# ESP_unit.net
KiCad netlist of a schematic drawn in Altium Designer
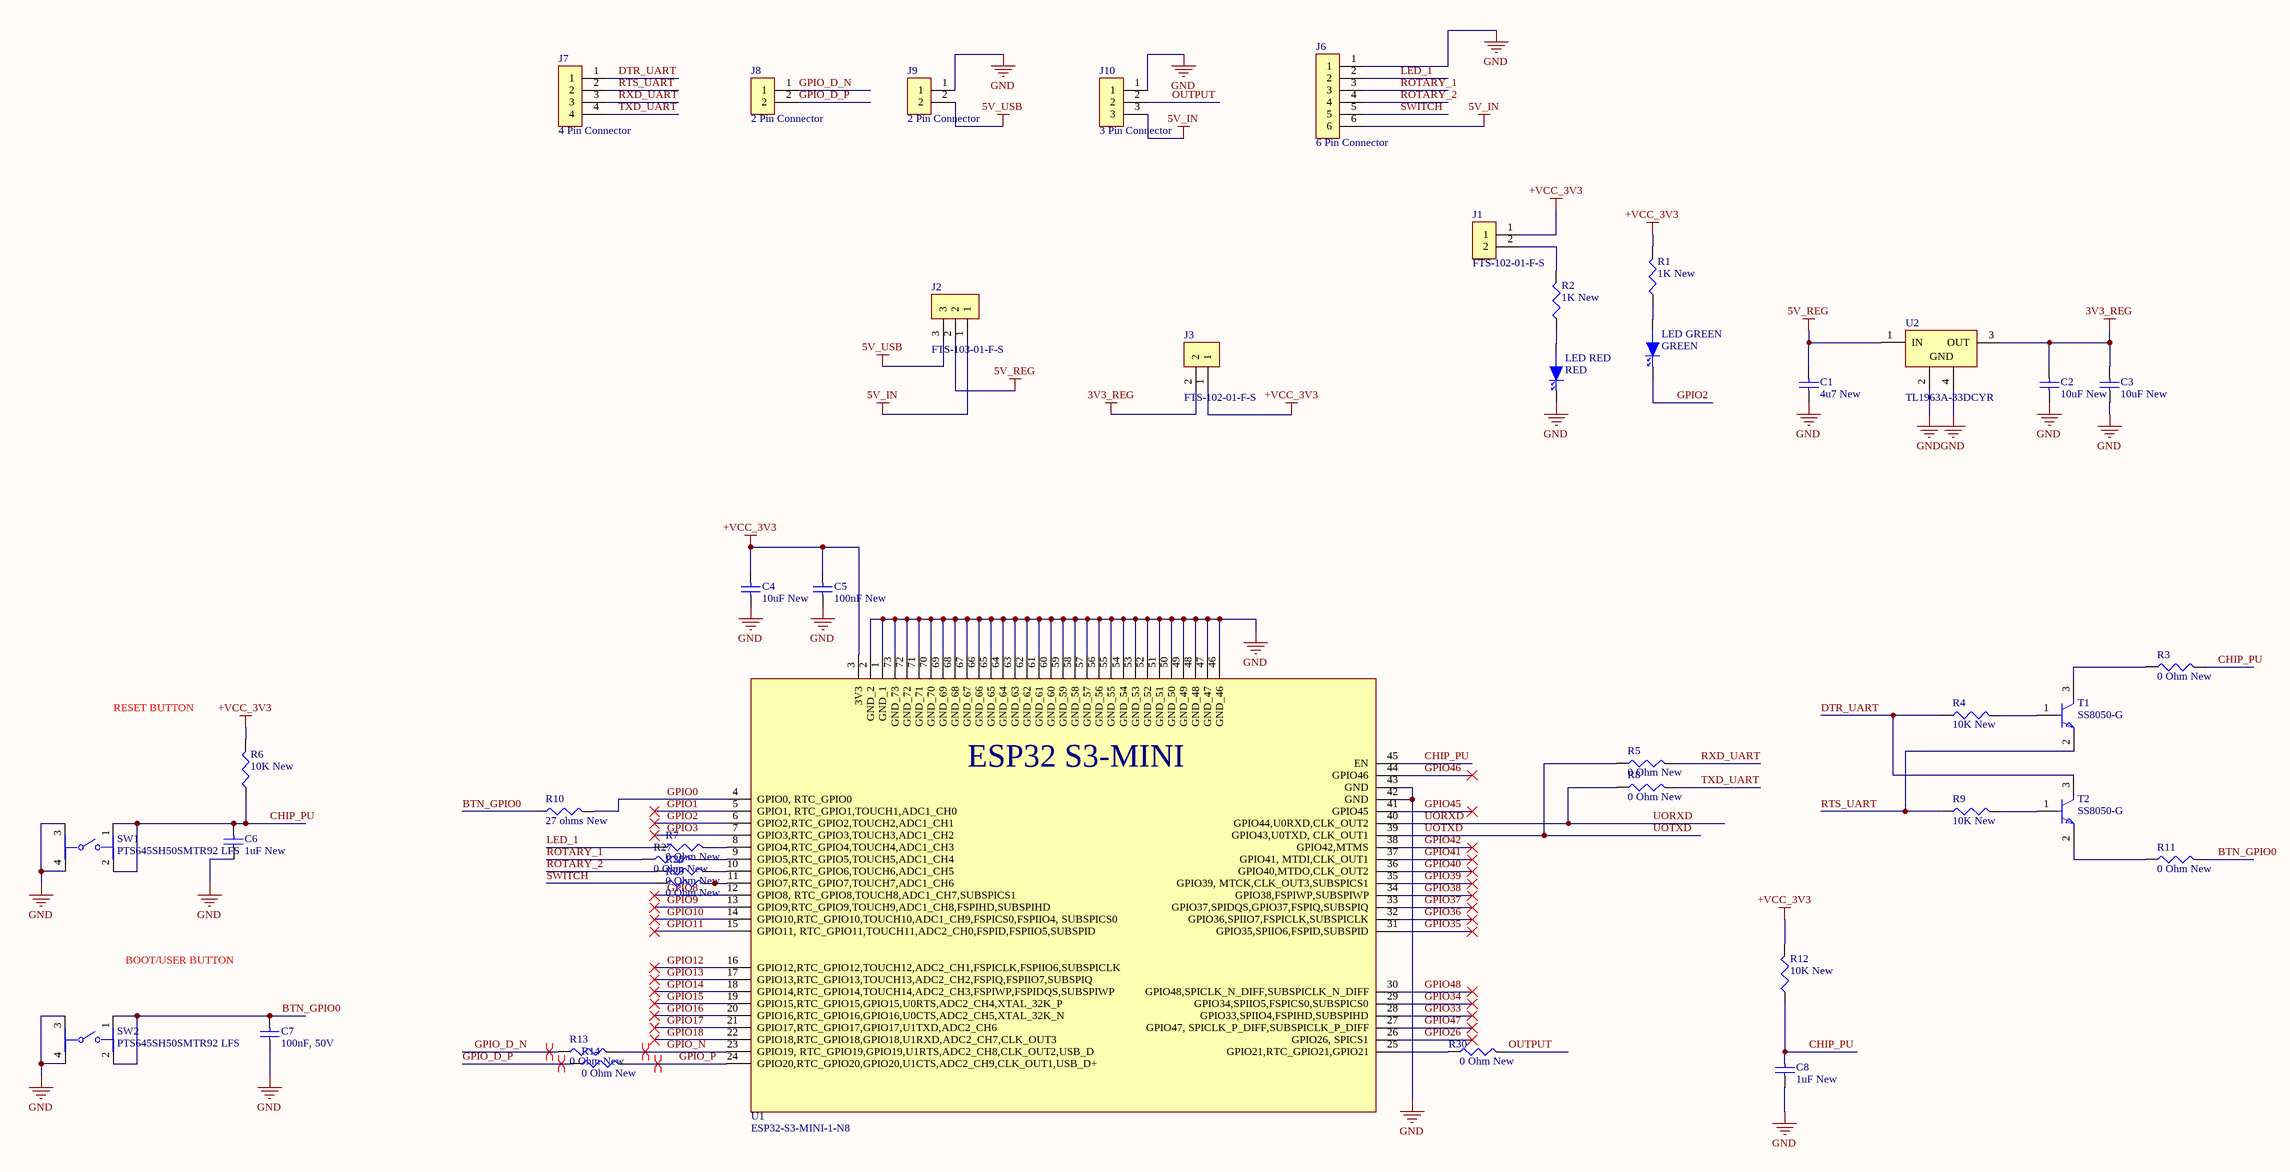
[diagram p0: ESP unit.SchDoc]

(export (version "E")
  (design (tool "Eeschema 10.0.6"))
  (components
    (comp (ref "C1")
      (value "4u7 New")
      (footprint "FP-CC0805-0_85-IPC_A")
      (fields
        (field (name "MANUFACTURER") "Yageo")
        (field (name "MANUFACTURER PART NUMBER") "CC0805KKX5R8BB475")
        (field (name "LCSC PART NUMBER") "C132173")
      )
      (libsource (lib "Schlib1") (part "CC0805KKX5R8BB475"))
    )
    (comp (ref "C2")
      (value "10uF New")
      (footprint "FP-CC0805-0_85-IPC_A")
      (fields
        (field (name "MANUFACTURER") "Yageo")
        (field (name "MANUFACTURER PART NUMBER") "CC0805ZKY5V6BB106")
        (field (name "LCSC PART NUMBER") "C88484")
      )
      (libsource (lib "Schlib1") (part "CC0805ZKY5V6BB106"))
    )
    (comp (ref "C3")
      (value "10uF New")
      (footprint "FP-CC0805-0_85-IPC_A")
      (fields
        (field (name "MANUFACTURER") "Yageo")
        (field (name "MANUFACTURER PART NUMBER") "CC0805ZKY5V6BB106")
        (field (name "LCSC PART NUMBER") "C88484")
      )
      (libsource (lib "Schlib1") (part "CC0805ZKY5V6BB106"))
    )
    (comp (ref "C4")
      (value "10uF New")
      (footprint "FP-CC0805-0_85-IPC_A")
      (fields
        (field (name "MANUFACTURER") "Yageo")
        (field (name "MANUFACTURER PART NUMBER") "CC0805ZKY5V6BB106")
        (field (name "LCSC PART NUMBER") "C88484")
      )
      (libsource (lib "Schlib1") (part "CC0805ZKY5V6BB106"))
    )
    (comp (ref "C5")
      (value "100nF New")
      (footprint "FP-CC0805-0_85-IPC_A")
      (fields
        (field (name "MANUFACTURER") "Yageo")
        (field (name "MANUFACTURER PART NUMBER") "CC0805KRX7R9BB104")
        (field (name "LCSC PART NUMBER") "C49678")
      )
      (libsource (lib "Schlib1") (part "CC0805KRX7R9BB104"))
    )
    (comp (ref "C6")
      (value "1uF New")
      (footprint "FP-CC0805-0_85-IPC_A")
      (fields
        (field (name "MANUFACTURER") "Yageo")
        (field (name "MANUFACTURER PART NUMBER") "CC0805KKX7R7BB105")
        (field (name "LCSC PART NUMBER") "C94122")
      )
      (libsource (lib "Schlib1") (part "CC0805KKX7R7BB105"))
    )
    (comp (ref "C7")
      (value "100nF, 50V")
      (footprint "CAPC1005X55N")
      (description "CAP CER 0.1UF 50V X7R 0402")
      (fields
        (field (name "MANUFACTURER") "Samsung")
        (field (name "MANUFACTURER PART NUMBER") "CL05B104KB54PNC")
      )
      (libsource (lib "Schlib1") (part "CL05B104KB54PNC"))
    )
    (comp (ref "C8")
      (value "1uF New")
      (footprint "FP-CC0805-0_85-IPC_A")
      (fields
        (field (name "MANUFACTURER") "Yageo")
        (field (name "MANUFACTURER PART NUMBER") "CC0805KKX7R7BB105")
        (field (name "LCSC PART NUMBER") "C94122")
      )
      (libsource (lib "Schlib1") (part "CC0805KKX7R7BB105"))
    )
    (comp (ref "J1")
      (value "FTS-102-01-F-S")
      (footprint "2 Pin Connector Jumper")
      (description "CONN HEADER VERT 2POS 1.27MM")
      (fields (field (name "MANUFACTURER") "Samtec") (field (name "LCSC PART NUMBER") "C6045317"))
      (libsource (lib "Schlib1") (part "FTS-102-01-F-S"))
    )
    (comp (ref "J2")
      (value "FTS-103-01-F-S")
      (footprint "3 Pin Connector Jumper - duplicate")
      (description "CONN HEADER VERT 3POS 1.27MM")
      (fields (field (name "MANUFACTURER") "Samtec") (field (name "LCSC PART NUMBER") "C3333578"))
      (libsource (lib "Schlib1") (part "FTS-103-01-F-S"))
    )
    (comp (ref "J3")
      (value "FTS-102-01-F-S")
      (footprint "2 Pin Connector Jumper")
      (description "CONN HEADER VERT 2POS 1.27MM")
      (fields (field (name "MANUFACTURER") "Samtec") (field (name "LCSC PART NUMBER") "C6045317"))
      (libsource (lib "") (part "FTS-102-01-F-S_1"))
    )
    (comp (ref "J6")
      (value "6 Pin Connector")
      (footprint "SAMTEC_HTSW-106-07-G-S")
      (fields
        (field (name "MANUFACTURER") "Samtec")
        (field (name "MANUFACTURER PART NUMBER") "HTSW-106-07-G-S")
        (field (name "LCSC PART NUMBER") "C3334125")
      )
      (libsource (lib "Schlib1") (part "HTSW-106-07-G-S"))
    )
    (comp (ref "J7")
      (value "4 Pin Connector")
      (footprint "SAMTEC_HTSW-104-07-G-S")
      (fields
        (field (name "MANUFACTURER") "Samtec")
        (field (name "MANUFACTURER PART NUMBER") "HTSW-104-07-G-S")
        (field (name "LCSC PART NUMBER") "C3335226")
      )
      (libsource (lib "Schlib1") (part "HTSW-104-07-G-S"))
    )
    (comp (ref "J8")
      (value "2 Pin Connector")
      (footprint "SAMTEC_HTSW-102-07-G-S")
      (description "Board Connector, 2 Contact(s), 1 Row(s), Male, Straight, 0.1 inch Pitch, Solder Terminal")
      (fields
        (field (name "MANUFACTURER") "Samtec")
        (field (name "MANUFACTURER PART NUMBER") "HTSW-102-07-G-S")
      )
      (libsource (lib "Schlib1") (part "HTSW-102-07-G-S"))
    )
    (comp (ref "J9")
      (value "2 Pin Connector")
      (footprint "SAMTEC_HTSW-102-07-G-S")
      (description "Board Connector, 2 Contact(s), 1 Row(s), Male, Straight, 0.1 inch Pitch, Solder Terminal")
      (fields
        (field (name "MANUFACTURER") "Samtec")
        (field (name "MANUFACTURER PART NUMBER") "HTSW-102-07-G-S")
      )
      (libsource (lib "Schlib1") (part "HTSW-102-07-G-S"))
    )
    (comp (ref "J10")
      (value "3 Pin Connector")
      (footprint "SAMTEC_HTSW-103-XX-X-S")
      (fields
        (field (name "MANUFACTURER") "Samtec")
        (field (name "MANUFACTURER PART NUMBER") "HTSW-103-07-G-S")
        (field (name "LCSC PART NUMBER") "C5714562")
      )
      (libsource (lib "Schlib1") (part "HTSW-103-07-G-S"))
    )
    (comp (ref "LED GREEN")
      (value "GREEN")
      (footprint "LED 0402G")
      (description "LED YLW-GRN 0402 SMD")
      (fields
        (field (name "MANUFACTURER") "Vishay")
        (field (name "MANUFACTURER PART NUMBER") "VLMG1500-GS08")
      )
      (libsource (lib "Schlib1") (part "VLMG1500-GS08"))
    )
    (comp (ref "LED RED")
      (value "RED")
      (footprint "LED 0402R")
      (description "LED RED 0402 SMD")
      (fields
        (field (name "MANUFACTURER") "Vishay")
        (field (name "MANUFACTURER PART NUMBER") "VLMS1500-GS08")
      )
      (libsource (lib "Schlib1") (part "VLMS1500-GS08"))
    )
    (comp (ref "R1")
      (value "1K New")
      (footprint "RESC2012X60N")
      (fields
        (field (name "MANUFACTURER") "Yageo")
        (field (name "MANUFACTURER PART NUMBER") "RC0805FR-071KL")
        (field (name "TOLERANCE") "1%")
      )
      (libsource (lib "Schlib1") (part "RC0805FR-071KL"))
    )
    (comp (ref "R2")
      (value "1K New")
      (footprint "RESC2012X60N")
      (fields
        (field (name "MANUFACTURER") "Yageo")
        (field (name "MANUFACTURER PART NUMBER") "RC0805FR-071KL")
        (field (name "TOLERANCE") "1%")
      )
      (libsource (lib "Schlib1") (part "RC0805FR-071KL"))
    )
    (comp (ref "R3")
      (value "0 Ohm New")
      (footprint "RESC2012X60N")
      (description "125mW Thick Film Resistors 150V ±5% 0Ω 0805 Chip Resistor - Surface Mount ROHS")
      (fields
        (field (name "MANUFACTURER") "Yageo")
        (field (name "MANUFACTURER PART NUMBER") "RC0805JR-070RL")
      )
      (libsource (lib "Schlib1") (part "RC0805JR-070RL"))
    )
    (comp (ref "R4")
      (value "10K New")
      (footprint "RESC2012X60N")
      (fields
        (field (name "MANUFACTURER") "Yageo")
        (field (name "MANUFACTURER PART NUMBER") "RE0805FRE0710KL")
        (field (name "TOLERANCE") "1%")
      )
      (libsource (lib "Schlib1") (part "RE0805FRE0710KL"))
    )
    (comp (ref "R5")
      (value "0 Ohm New")
      (footprint "RESC2012X60N")
      (description "125mW Thick Film Resistors 150V ±5% 0Ω 0805 Chip Resistor - Surface Mount ROHS")
      (fields
        (field (name "MANUFACTURER") "Yageo")
        (field (name "MANUFACTURER PART NUMBER") "RC0805JR-070RL")
      )
      (libsource (lib "Schlib1") (part "RC0805JR-070RL"))
    )
    (comp (ref "R6")
      (value "10K New")
      (footprint "RESC2012X60N")
      (fields
        (field (name "MANUFACTURER") "Yageo")
        (field (name "MANUFACTURER PART NUMBER") "RE0805FRE0710KL")
        (field (name "TOLERANCE") "1%")
      )
      (libsource (lib "Schlib1") (part "RE0805FRE0710KL"))
    )
    (comp (ref "R7")
      (value "0 Ohm New")
      (footprint "RESC2012X60N")
      (description "125mW Thick Film Resistors 150V ±5% 0Ω 0805 Chip Resistor - Surface Mount ROHS")
      (fields
        (field (name "MANUFACTURER") "Yageo")
        (field (name "MANUFACTURER PART NUMBER") "RC0805JR-070RL")
      )
      (libsource (lib "Schlib1") (part "RC0805JR-070RL"))
    )
    (comp (ref "R8")
      (value "0 Ohm New")
      (footprint "RESC2012X60N")
      (description "125mW Thick Film Resistors 150V ±5% 0Ω 0805 Chip Resistor - Surface Mount ROHS")
      (fields
        (field (name "MANUFACTURER") "Yageo")
        (field (name "MANUFACTURER PART NUMBER") "RC0805JR-070RL")
      )
      (libsource (lib "Schlib1") (part "RC0805JR-070RL"))
    )
    (comp (ref "R9")
      (value "10K New")
      (footprint "RESC2012X60N")
      (fields
        (field (name "MANUFACTURER") "Yageo")
        (field (name "MANUFACTURER PART NUMBER") "RE0805FRE0710KL")
        (field (name "TOLERANCE") "1%")
      )
      (libsource (lib "Schlib1") (part "RE0805FRE0710KL"))
    )
    (comp (ref "R10")
      (value "27 ohms New")
      (footprint "RESC2012X60N")
      (fields
        (field (name "MANUFACTURER") "Yageo")
        (field (name "MANUFACTURER PART NUMBER") "RC0805FR-0727RL")
        (field (name "TOLERANCE") "1%")
      )
      (libsource (lib "Schlib1") (part "RC0805FR-0727RL"))
    )
    (comp (ref "R11")
      (value "0 Ohm New")
      (footprint "RESC2012X60N")
      (description "125mW Thick Film Resistors 150V ±5% 0Ω 0805 Chip Resistor - Surface Mount ROHS")
      (fields
        (field (name "MANUFACTURER") "Yageo")
        (field (name "MANUFACTURER PART NUMBER") "RC0805JR-070RL")
      )
      (libsource (lib "Schlib1") (part "RC0805JR-070RL"))
    )
    (comp (ref "R12")
      (value "10K New")
      (footprint "RESC2012X60N")
      (fields
        (field (name "MANUFACTURER") "Yageo")
        (field (name "MANUFACTURER PART NUMBER") "RE0805FRE0710KL")
        (field (name "TOLERANCE") "1%")
      )
      (libsource (lib "Schlib1") (part "RE0805FRE0710KL"))
    )
    (comp (ref "R13")
      (value "0 Ohm New")
      (footprint "RESC2012X60N")
      (description "125mW Thick Film Resistors 150V ±5% 0Ω 0805 Chip Resistor - Surface Mount ROHS")
      (fields
        (field (name "MANUFACTURER") "Yageo")
        (field (name "MANUFACTURER PART NUMBER") "RC0805JR-070RL")
      )
      (libsource (lib "Schlib1") (part "RC0805JR-070RL"))
    )
    (comp (ref "R14")
      (value "0 Ohm New")
      (footprint "RESC2012X60N")
      (description "125mW Thick Film Resistors 150V ±5% 0Ω 0805 Chip Resistor - Surface Mount ROHS")
      (fields
        (field (name "MANUFACTURER") "Yageo")
        (field (name "MANUFACTURER PART NUMBER") "RC0805JR-070RL")
      )
      (libsource (lib "Schlib1") (part "RC0805JR-070RL"))
    )
    (comp (ref "R27")
      (value "0 Ohm New")
      (footprint "RESC2012X60N")
      (description "125mW Thick Film Resistors 150V ±5% 0Ω 0805 Chip Resistor - Surface Mount ROHS")
      (fields
        (field (name "MANUFACTURER") "Yageo")
        (field (name "MANUFACTURER PART NUMBER") "RC0805JR-070RL")
      )
      (libsource (lib "Schlib1") (part "RC0805JR-070RL"))
    )
    (comp (ref "R28")
      (value "0 Ohm New")
      (footprint "RESC2012X60N")
      (description "125mW Thick Film Resistors 150V ±5% 0Ω 0805 Chip Resistor - Surface Mount ROHS")
      (fields
        (field (name "MANUFACTURER") "Yageo")
        (field (name "MANUFACTURER PART NUMBER") "RC0805JR-070RL")
      )
      (libsource (lib "Schlib1") (part "RC0805JR-070RL"))
    )
    (comp (ref "R29")
      (value "0 Ohm New")
      (footprint "RESC2012X60N")
      (description "125mW Thick Film Resistors 150V ±5% 0Ω 0805 Chip Resistor - Surface Mount ROHS")
      (fields
        (field (name "MANUFACTURER") "Yageo")
        (field (name "MANUFACTURER PART NUMBER") "RC0805JR-070RL")
      )
      (libsource (lib "Schlib1") (part "RC0805JR-070RL"))
    )
    (comp (ref "R30")
      (value "0 Ohm New")
      (footprint "RESC2012X60N")
      (description "125mW Thick Film Resistors 150V ±5% 0Ω 0805 Chip Resistor - Surface Mount ROHS")
      (fields
        (field (name "MANUFACTURER") "Yageo")
        (field (name "MANUFACTURER PART NUMBER") "RC0805JR-070RL")
      )
      (libsource (lib "Schlib1") (part "RC0805JR-070RL"))
    )
    (comp (ref "SW1")
      (value "PTS645SH50SMTR92 LFS")
      (footprint "FP-PTS645SH50SMTR92LFS-MFG")
      (description "SWITCH TACTILE SPST-NO 0.05A 12V")
      (fields
        (field (name "MANUFACTURER") "ITT C&K")
        (field (name "MANUFACTURER PART NUMBER") "PTS645SH50SMTR92LFS")
      )
      (libsource (lib "Schlib1") (part "PTS645SH50SMTR92LFS"))
    )
    (comp (ref "SW2")
      (value "PTS645SH50SMTR92 LFS")
      (footprint "FP-PTS645SH50SMTR92LFS-MFG")
      (description "SWITCH TACTILE SPST-NO 0.05A 12V")
      (fields
        (field (name "MANUFACTURER") "ITT C&K")
        (field (name "MANUFACTURER PART NUMBER") "PTS645SH50SMTR92LFS")
      )
      (libsource (lib "Schlib1") (part "PTS645SH50SMTR92LFS"))
    )
    (comp (ref "T1")
      (value "SS8050-G")
      (footprint "FP-SS8050-G-IPC_B")
      (description "TRANS NPN 25V 1.5A SOT-23-3")
      (fields (field (name "MANUFACTURER") "Comchip") (field (name "LCSC PART NUMBER") "C164886"))
      (libsource (lib "Schlib1") (part "SS8050-G"))
    )
    (comp (ref "T2")
      (value "SS8050-G")
      (footprint "FP-SS8050-G-IPC_B")
      (description "TRANS NPN 25V 1.5A SOT-23-3")
      (fields (field (name "MANUFACTURER") "Comchip") (field (name "LCSC PART NUMBER") "C164886"))
      (libsource (lib "Schlib1") (part "SS8050-G"))
    )
    (comp (ref "U1")
      (value "ESP32-S3-MINI-1-N8")
      (footprint "XCVR_ESP32-S3-MINI-1-N8")
      (description "SMD module, ESP32-S3FN8, 8 MB SPI flash, PCB antenna")
      (fields (field (name "MANUFACTURER") "Espressif Systems") (field (name "LCSC PART NUMBER") "C2913206"))
      (libsource (lib "Schlib1") (part "ESP32-S3-MINI-1-N8"))
    )
    (comp (ref "U2")
      (value "TL1963A-33DCYR")
      (footprint "DCY0004A_N")
      (description "IC REG LIN 3.3V 1.5A SOT-223-4")
      (fields (field (name "MANUFACTURER") "Texas Instruments") (field (name "LCSC PART NUMBER") "C181262"))
      (libsource (lib "Schlib1") (part "TL1963A-33DCYR"))
    )
  )
  (nets
    (net (code "1") (name "+VCC_3V3") (class "Default")
      (node (ref "C4") (pin "2") (pinfunction "2_2") (pintype "passive"))
      (node (ref "C5") (pin "2") (pinfunction "2_2") (pintype "passive"))
      (node (ref "J1") (pin "1") (pinfunction "1_1") (pintype "passive"))
      (node (ref "J3") (pin "1") (pinfunction "1_1") (pintype "passive"))
      (node (ref "R1") (pin "2") (pinfunction "2_2") (pintype "passive"))
      (node (ref "R12") (pin "2") (pinfunction "2_2") (pintype "passive"))
      (node (ref "R6") (pin "2") (pinfunction "2_2") (pintype "passive"))
      (node (ref "U1") (pin "3") (pinfunction "3V3_3") (pintype "passive"))
    )
    (net (code "2") (name "/BTN_GPIO0") (class "Default")
      (node (ref "C7") (pin "2") (pinfunction "2_2") (pintype "passive"))
      (node (ref "R10") (pin "1") (pinfunction "1_1") (pintype "passive"))
      (node (ref "R11") (pin "2") (pinfunction "2_2") (pintype "passive"))
      (node (ref "SW2") (pin "1") (pinfunction "1_1") (pintype "passive"))
      (node (ref "SW2") (pin "2") (pinfunction "2_2") (pintype "passive"))
    )
    (net (code "3") (name "/CHIP_PU") (class "Default")
      (node (ref "C6") (pin "2") (pinfunction "2_2") (pintype "passive"))
      (node (ref "C8") (pin "2") (pinfunction "2_2") (pintype "passive"))
      (node (ref "R12") (pin "1") (pinfunction "1_1") (pintype "passive"))
      (node (ref "R3") (pin "2") (pinfunction "2_2") (pintype "passive"))
      (node (ref "R6") (pin "1") (pinfunction "1_1") (pintype "passive"))
      (node (ref "SW1") (pin "1") (pinfunction "1_1") (pintype "passive"))
      (node (ref "SW1") (pin "2") (pinfunction "2_2") (pintype "passive"))
      (node (ref "U1") (pin "45") (pinfunction "EN_45") (pintype "passive"))
    )
    (net (code "4") (name "/DTR_UART") (class "Default")
      (node (ref "J7") (pin "1") (pinfunction "1_1") (pintype "passive"))
      (node (ref "R4") (pin "1") (pinfunction "1_1") (pintype "passive"))
      (node (ref "T2") (pin "3") (pinfunction "C_3") (pintype "passive"))
    )
    (net (code "5") (name "/GPIO0") (class "Default")
      (node (ref "R10") (pin "2") (pinfunction "2_2") (pintype "passive"))
      (node (ref "U1") (pin "4") (pinfunction "GPIO0,_RTC_GPIO0_4") (pintype "passive"))
    )
    (net (code "6") (name "/GPIO1") (class "Default")
      (node (ref "U1") (pin "5") (pinfunction "GPIO1,_RTC_GPIO1,TOUCH1,ADC1_CH0_5") (pintype "passive+no_connect"))
    )
    (net (code "7") (name "/GPIO2") (class "Default")
      (node (ref "LED GREEN") (pin "1") (pinfunction "1_1") (pintype "passive"))
      (node (ref "U1") (pin "6") (pinfunction "GPIO2,RTC_GPIO2,TOUCH2,ADC1_CH1_6") (pintype "passive"))
    )
    (net (code "8") (name "/GPIO3") (class "Default")
      (node (ref "U1") (pin "7") (pinfunction "GPIO3,RTC_GPIO3,TOUCH3,ADC1_CH2_7") (pintype "passive+no_connect"))
    )
    (net (code "9") (name "/GPIO8") (class "Default")
      (node (ref "U1") (pin "12") (pinfunction "GPIO8,_RTC_GPIO8,TOUCH8,ADC1_CH7,SUBSPICS1_12") (pintype "passive+no_connect"))
    )
    (net (code "10") (name "/GPIO9") (class "Default")
      (node (ref "U1") (pin "13") (pinfunction "GPIO9,RTC_GPIO9,TOUCH9,ADC1_CH8,FSPIHD,SUBSPIHD_13") (pintype "passive+no_connect"))
    )
    (net (code "11") (name "/GPIO10") (class "Default")
      (node (ref "U1") (pin "14") (pinfunction "GPIO10,RTC_GPIO10,TOUCH10,ADC1_CH9,FSPICS0,FSPIIO4,_SUBSPICS0_14") (pintype "passive+no_connect"))
    )
    (net (code "12") (name "/GPIO11") (class "Default")
      (node (ref "U1") (pin "15") (pinfunction "GPIO11,_RTC_GPIO11,TOUCH11,ADC2_CH0,FSPID,FSPIIO5,SUBSPID_15") (pintype "passive+no_connect"))
    )
    (net (code "13") (name "/GPIO12") (class "Default")
      (node (ref "U1") (pin "16") (pinfunction "GPIO12,RTC_GPIO12,TOUCH12,ADC2_CH1,FSPICLK,FSPIIO6,SUBSPICLK_16") (pintype "passive+no_connect"))
    )
    (net (code "14") (name "/GPIO13") (class "Default")
      (node (ref "U1") (pin "17") (pinfunction "GPIO13,RTC_GPIO13,TOUCH13,ADC2_CH2,FSPIQ,FSPIIO7,SUBSPIQ_17") (pintype "passive+no_connect"))
    )
    (net (code "15") (name "/GPIO14") (class "Default")
      (node (ref "U1") (pin "18") (pinfunction "GPIO14,RTC_GPIO14,TOUCH14,ADC2_CH3,FSPIWP,FSPIDQS,SUBSPIWP_18") (pintype "passive+no_connect"))
    )
    (net (code "16") (name "/GPIO15") (class "Default")
      (node (ref "U1") (pin "19") (pinfunction "GPIO15,RTC_GPIO15,GPIO15,U0RTS,ADC2_CH4,XTAL_32K_P_19") (pintype "passive+no_connect"))
    )
    (net (code "17") (name "/GPIO16") (class "Default")
      (node (ref "U1") (pin "20") (pinfunction "GPIO16,RTC_GPIO16,GPIO16,U0CTS,ADC2_CH5,XTAL_32K_N_20") (pintype "passive+no_connect"))
    )
    (net (code "18") (name "/GPIO17") (class "Default")
      (node (ref "U1") (pin "21") (pinfunction "GPIO17,RTC_GPIO17,GPIO17,U1TXD,ADC2_CH6_21") (pintype "passive+no_connect"))
    )
    (net (code "19") (name "/GPIO18") (class "Default")
      (node (ref "U1") (pin "22") (pinfunction "GPIO18,RTC_GPIO18,GPIO18,U1RXD,ADC2_CH7,CLK_OUT3_22") (pintype "passive+no_connect"))
    )
    (net (code "20") (name "/GPIO26") (class "Default")
      (node (ref "U1") (pin "26") (pinfunction "GPIO26,_SPICS1_26") (pintype "passive+no_connect"))
    )
    (net (code "21") (name "/GPIO33") (class "Default")
      (node (ref "U1") (pin "28") (pinfunction "GPIO33,SPIIO4,FSPIHD,SUBSPIHD_28") (pintype "passive+no_connect"))
    )
    (net (code "22") (name "/GPIO34") (class "Default")
      (node (ref "U1") (pin "29") (pinfunction "GPIO34,SPIIO5,FSPICS0,SUBSPICS0_29") (pintype "passive+no_connect"))
    )
    (net (code "23") (name "/GPIO35") (class "Default")
      (node (ref "U1") (pin "31") (pinfunction "GPIO35,SPIIO6,FSPID,SUBSPID_31") (pintype "passive+no_connect"))
    )
    (net (code "24") (name "/GPIO36") (class "Default")
      (node (ref "U1") (pin "32") (pinfunction "GPIO36,SPIIO7,FSPICLK,SUBSPICLK_32") (pintype "passive+no_connect"))
    )
    (net (code "25") (name "/GPIO37") (class "Default")
      (node (ref "U1") (pin "33") (pinfunction "GPIO37,SPIDQS,GPIO37,FSPIQ,SUBSPIQ_33") (pintype "passive+no_connect"))
    )
    (net (code "26") (name "/GPIO38") (class "Default")
      (node (ref "U1") (pin "34") (pinfunction "GPIO38,FSPIWP,SUBSPIWP_34") (pintype "passive+no_connect"))
    )
    (net (code "27") (name "/GPIO39") (class "Default")
      (node (ref "U1") (pin "35") (pinfunction "GPIO39,_MTCK,CLK_OUT3,SUBSPICS1_35") (pintype "passive+no_connect"))
    )
    (net (code "28") (name "/GPIO40") (class "Default")
      (node (ref "U1") (pin "36") (pinfunction "GPIO40,MTDO,CLK_OUT2_36") (pintype "passive+no_connect"))
    )
    (net (code "29") (name "/GPIO41") (class "Default")
      (node (ref "U1") (pin "37") (pinfunction "GPIO41,_MTDI,CLK_OUT1_37") (pintype "passive+no_connect"))
    )
    (net (code "30") (name "/GPIO42") (class "Default")
      (node (ref "U1") (pin "38") (pinfunction "GPIO42,MTMS_38") (pintype "passive+no_connect"))
    )
    (net (code "31") (name "/GPIO45") (class "Default")
      (node (ref "U1") (pin "41") (pinfunction "GPIO45_41") (pintype "passive+no_connect"))
    )
    (net (code "32") (name "/GPIO46") (class "Default")
      (node (ref "U1") (pin "44") (pinfunction "GPIO46_44") (pintype "passive+no_connect"))
    )
    (net (code "33") (name "/GPIO47") (class "Default")
      (node (ref "U1") (pin "27") (pinfunction "GPIO47,_SPICLK_P_DIFF,SUBSPICLK_P_DIFF_27") (pintype "passive+no_connect"))
    )
    (net (code "34") (name "/GPIO48") (class "Default")
      (node (ref "U1") (pin "30") (pinfunction "GPIO48,SPICLK_N_DIFF,SUBSPICLK_N_DIFF_30") (pintype "passive+no_connect"))
    )
    (net (code "35") (name "/GPIO_D_N") (class "Default")
      (node (ref "J8") (pin "1") (pinfunction "1_1") (pintype "passive"))
      (node (ref "R13") (pin "1") (pinfunction "1_1") (pintype "passive"))
    )
    (net (code "36") (name "/GPIO_D_P") (class "Default")
      (node (ref "J8") (pin "2") (pinfunction "2_2") (pintype "passive"))
      (node (ref "R14") (pin "1") (pinfunction "1_1") (pintype "passive"))
    )
    (net (code "37") (name "/GPIO_N") (class "Default")
      (node (ref "R13") (pin "2") (pinfunction "2_2") (pintype "passive"))
      (node (ref "U1") (pin "23") (pinfunction "GPIO19,_RTC_GPIO19,GPIO19,U1RTS,ADC2_CH8,CLK_OUT2,USB_D_23") (pintype "passive"))
    )
    (net (code "38") (name "/GPIO_P") (class "Default")
      (node (ref "R14") (pin "2") (pinfunction "2_2") (pintype "passive"))
      (node (ref "U1") (pin "24") (pinfunction "GPIO20,RTC_GPIO20,GPIO20,U1CTS,ADC2_CH9,CLK_OUT1,USB_D+_24") (pintype "passive"))
    )
    (net (code "39") (name "/LED_1") (class "Default")
      (node (ref "J6") (pin "2") (pinfunction "2_2") (pintype "passive"))
      (node (ref "R7") (pin "1") (pinfunction "1_1") (pintype "passive"))
    )
    (net (code "40") (name "/OUTPUT") (class "Default")
      (node (ref "J10") (pin "2") (pinfunction "2_2") (pintype "passive"))
      (node (ref "R30") (pin "2") (pinfunction "2_2") (pintype "passive"))
    )
    (net (code "41") (name "/ROTARY_1") (class "Default")
      (node (ref "J6") (pin "3") (pinfunction "3_3") (pintype "passive"))
      (node (ref "R27") (pin "1") (pinfunction "1_1") (pintype "passive"))
    )
    (net (code "42") (name "/ROTARY_2") (class "Default")
      (node (ref "J6") (pin "4") (pinfunction "4_4") (pintype "passive"))
      (node (ref "R28") (pin "1") (pinfunction "1_1") (pintype "passive"))
    )
    (net (code "43") (name "/RTS_UART") (class "Default")
      (node (ref "J7") (pin "2") (pinfunction "2_2") (pintype "passive"))
      (node (ref "R9") (pin "1") (pinfunction "1_1") (pintype "passive"))
      (node (ref "T1") (pin "2") (pinfunction "E_2") (pintype "passive"))
    )
    (net (code "44") (name "/RXD_UART") (class "Default")
      (node (ref "J7") (pin "3") (pinfunction "3_3") (pintype "passive"))
      (node (ref "R5") (pin "2") (pinfunction "2_2") (pintype "passive"))
    )
    (net (code "45") (name "/SWITCH") (class "Default")
      (node (ref "J6") (pin "5") (pinfunction "5_5") (pintype "passive"))
      (node (ref "R29") (pin "1") (pinfunction "1_1") (pintype "passive"))
    )
    (net (code "46") (name "/TXD_UART") (class "Default")
      (node (ref "J7") (pin "4") (pinfunction "4_4") (pintype "passive"))
      (node (ref "R8") (pin "2") (pinfunction "2_2") (pintype "passive"))
    )
    (net (code "47") (name "/UORXD") (class "Default")
      (node (ref "R8") (pin "1") (pinfunction "1_1") (pintype "passive"))
      (node (ref "U1") (pin "40") (pinfunction "GPIO44,U0RXD,CLK_OUT2_40") (pintype "passive"))
    )
    (net (code "48") (name "/UOTXD") (class "Default")
      (node (ref "R5") (pin "1") (pinfunction "1_1") (pintype "passive"))
      (node (ref "U1") (pin "39") (pinfunction "GPIO43,U0TXD,_CLK_OUT1_39") (pintype "passive"))
    )
    (net (code "49") (name "3V3_REG") (class "Default")
      (node (ref "C2") (pin "2") (pinfunction "2_2") (pintype "passive"))
      (node (ref "C3") (pin "2") (pinfunction "2_2") (pintype "passive"))
      (node (ref "J3") (pin "2") (pinfunction "2_2") (pintype "passive"))
      (node (ref "U2") (pin "3") (pinfunction "OUT_3") (pintype "power_in"))
    )
    (net (code "50") (name "5V_IN") (class "Default")
      (node (ref "J10") (pin "3") (pinfunction "3_3") (pintype "passive"))
      (node (ref "J2") (pin "1") (pinfunction "1_1") (pintype "passive"))
      (node (ref "J6") (pin "6") (pinfunction "6_6") (pintype "passive"))
    )
    (net (code "51") (name "5V_REG") (class "Default")
      (node (ref "C1") (pin "2") (pinfunction "2_2") (pintype "passive"))
      (node (ref "J2") (pin "2") (pinfunction "2_2") (pintype "passive"))
      (node (ref "U2") (pin "1") (pinfunction "IN_1") (pintype "power_in"))
    )
    (net (code "52") (name "5V_USB") (class "Default")
      (node (ref "J2") (pin "3") (pinfunction "3_3") (pintype "passive"))
      (node (ref "J9") (pin "2") (pinfunction "2_2") (pintype "passive"))
    )
    (net (code "53") (name "GND") (class "Default")
      (node (ref "C1") (pin "1") (pinfunction "1_1") (pintype "passive"))
      (node (ref "C2") (pin "1") (pinfunction "1_1") (pintype "passive"))
      (node (ref "C3") (pin "1") (pinfunction "1_1") (pintype "passive"))
      (node (ref "C4") (pin "1") (pinfunction "1_1") (pintype "passive"))
      (node (ref "C5") (pin "1") (pinfunction "1_1") (pintype "passive"))
      (node (ref "C6") (pin "1") (pinfunction "1_1") (pintype "passive"))
      (node (ref "C7") (pin "1") (pinfunction "1_1") (pintype "passive"))
      (node (ref "C8") (pin "1") (pinfunction "1_1") (pintype "passive"))
      (node (ref "J10") (pin "1") (pinfunction "1_1") (pintype "passive"))
      (node (ref "J6") (pin "1") (pinfunction "1_1") (pintype "passive"))
      (node (ref "J9") (pin "1") (pinfunction "1_1") (pintype "passive"))
      (node (ref "LED RED") (pin "1") (pinfunction "1_1") (pintype "passive"))
      (node (ref "SW1") (pin "3") (pinfunction "3_3") (pintype "passive"))
      (node (ref "SW1") (pin "4") (pinfunction "4_4") (pintype "passive"))
      (node (ref "SW2") (pin "3") (pinfunction "3_3") (pintype "passive"))
      (node (ref "SW2") (pin "4") (pinfunction "4_4") (pintype "passive"))
      (node (ref "U1") (pin "1") (pinfunction "GND_1_1") (pintype "passive"))
      (node (ref "U1") (pin "2") (pinfunction "GND_2_2") (pintype "passive"))
      (node (ref "U1") (pin "42") (pinfunction "GND_42") (pintype "passive"))
      (node (ref "U1") (pin "43") (pinfunction "GND_43") (pintype "passive"))
      (node (ref "U1") (pin "46") (pinfunction "GND_46_46") (pintype "passive"))
      (node (ref "U1") (pin "47") (pinfunction "GND_47_47") (pintype "passive"))
      (node (ref "U1") (pin "48") (pinfunction "GND_48_48") (pintype "passive"))
      (node (ref "U1") (pin "49") (pinfunction "GND_49_49") (pintype "passive"))
      (node (ref "U1") (pin "50") (pinfunction "GND_50_50") (pintype "passive"))
      (node (ref "U1") (pin "51") (pinfunction "GND_51_51") (pintype "passive"))
      (node (ref "U1") (pin "52") (pinfunction "GND_52_52") (pintype "passive"))
      (node (ref "U1") (pin "53") (pinfunction "GND_53_53") (pintype "passive"))
      (node (ref "U1") (pin "54") (pinfunction "GND_54_54") (pintype "passive"))
      (node (ref "U1") (pin "55") (pinfunction "GND_55_55") (pintype "passive"))
      (node (ref "U1") (pin "56") (pinfunction "GND_56_56") (pintype "passive"))
      (node (ref "U1") (pin "57") (pinfunction "GND_57_57") (pintype "passive"))
      (node (ref "U1") (pin "58") (pinfunction "GND_58_58") (pintype "passive"))
      (node (ref "U1") (pin "59") (pinfunction "GND_59_59") (pintype "passive"))
      (node (ref "U1") (pin "60") (pinfunction "GND_60_60") (pintype "passive"))
      (node (ref "U1") (pin "61") (pinfunction "GND_61_61") (pintype "passive"))
      (node (ref "U1") (pin "62") (pinfunction "GND_62_62") (pintype "passive"))
      (node (ref "U1") (pin "63") (pinfunction "GND_63_63") (pintype "passive"))
      (node (ref "U1") (pin "64") (pinfunction "GND_64_64") (pintype "passive"))
      (node (ref "U1") (pin "65") (pinfunction "GND_65_65") (pintype "passive"))
      (node (ref "U1") (pin "66") (pinfunction "GND_66_66") (pintype "passive"))
      (node (ref "U1") (pin "67") (pinfunction "GND_67_67") (pintype "passive"))
      (node (ref "U1") (pin "68") (pinfunction "GND_68_68") (pintype "passive"))
      (node (ref "U1") (pin "69") (pinfunction "GND_69_69") (pintype "passive"))
      (node (ref "U1") (pin "70") (pinfunction "GND_70_70") (pintype "passive"))
      (node (ref "U1") (pin "71") (pinfunction "GND_71_71") (pintype "passive"))
      (node (ref "U1") (pin "72") (pinfunction "GND_72_72") (pintype "passive"))
      (node (ref "U1") (pin "73") (pinfunction "GND_73_73") (pintype "passive"))
      (node (ref "U2") (pin "2") (pinfunction "GND_2") (pintype "power_in"))
      (node (ref "U2") (pin "4") (pinfunction "GND_4") (pintype "power_in"))
    )
    (net (code "54") (name "Net-(J1-Pad2)") (class "Default")
      (node (ref "J1") (pin "2") (pinfunction "2_2") (pintype "passive"))
      (node (ref "R2") (pin "2") (pinfunction "2_2") (pintype "passive"))
    )
    (net (code "55") (name "Net-(LED GREEN-Pad2)") (class "Default")
      (node (ref "LED GREEN") (pin "2") (pinfunction "2_2") (pintype "passive"))
      (node (ref "R1") (pin "1") (pinfunction "1_1") (pintype "passive"))
    )
    (net (code "56") (name "Net-(LED RED-Pad2)") (class "Default")
      (node (ref "LED RED") (pin "2") (pinfunction "2_2") (pintype "passive"))
      (node (ref "R2") (pin "1") (pinfunction "1_1") (pintype "passive"))
    )
    (net (code "57") (name "Net-(T1-B)") (class "Default")
      (node (ref "R4") (pin "2") (pinfunction "2_2") (pintype "passive"))
      (node (ref "T1") (pin "1") (pinfunction "B_1") (pintype "passive"))
    )
    (net (code "58") (name "Net-(T1-C)") (class "Default")
      (node (ref "R3") (pin "1") (pinfunction "1_1") (pintype "passive"))
      (node (ref "T1") (pin "3") (pinfunction "C_3") (pintype "passive"))
    )
    (net (code "59") (name "Net-(T2-B)") (class "Default")
      (node (ref "R9") (pin "2") (pinfunction "2_2") (pintype "passive"))
      (node (ref "T2") (pin "1") (pinfunction "B_1") (pintype "passive"))
    )
    (net (code "60") (name "Net-(T2-E)") (class "Default")
      (node (ref "R11") (pin "1") (pinfunction "1_1") (pintype "passive"))
      (node (ref "T2") (pin "2") (pinfunction "E_2") (pintype "passive"))
    )
    (net (code "61") (name "Net-(U1-GPIO4,RTC_GPIO4,TOUCH4,ADC1_CH3)") (class "Default")
      (node (ref "R7") (pin "2") (pinfunction "2_2") (pintype "passive"))
      (node (ref "U1") (pin "8") (pinfunction "GPIO4,RTC_GPIO4,TOUCH4,ADC1_CH3_8") (pintype "passive"))
    )
    (net (code "62") (name "Net-(U1-GPIO5,RTC_GPIO5,TOUCH5,ADC1_CH4)") (class "Default")
      (node (ref "R27") (pin "2") (pinfunction "2_2") (pintype "passive"))
      (node (ref "U1") (pin "9") (pinfunction "GPIO5,RTC_GPIO5,TOUCH5,ADC1_CH4_9") (pintype "passive"))
    )
    (net (code "63") (name "Net-(U1-GPIO6,RTC_GPIO6,TOUCH6,ADC1_CH5)") (class "Default")
      (node (ref "R28") (pin "2") (pinfunction "2_2") (pintype "passive"))
      (node (ref "U1") (pin "10") (pinfunction "GPIO6,RTC_GPIO6,TOUCH6,ADC1_CH5_10") (pintype "passive"))
    )
    (net (code "64") (name "Net-(U1-GPIO7,RTC_GPIO7,TOUCH7,ADC1_CH6)") (class "Default")
      (node (ref "R29") (pin "2") (pinfunction "2_2") (pintype "passive"))
      (node (ref "U1") (pin "11") (pinfunction "GPIO7,RTC_GPIO7,TOUCH7,ADC1_CH6_11") (pintype "passive"))
    )
    (net (code "65") (name "Net-(U1-GPIO21,RTC_GPIO21,GPIO21)") (class "Default")
      (node (ref "R30") (pin "1") (pinfunction "1_1") (pintype "passive"))
      (node (ref "U1") (pin "25") (pinfunction "GPIO21,RTC_GPIO21,GPIO21_25") (pintype "passive"))
    )
  )
)
